# D_GND.net
KiCad netlist of a schematic drawn in Altium Designer
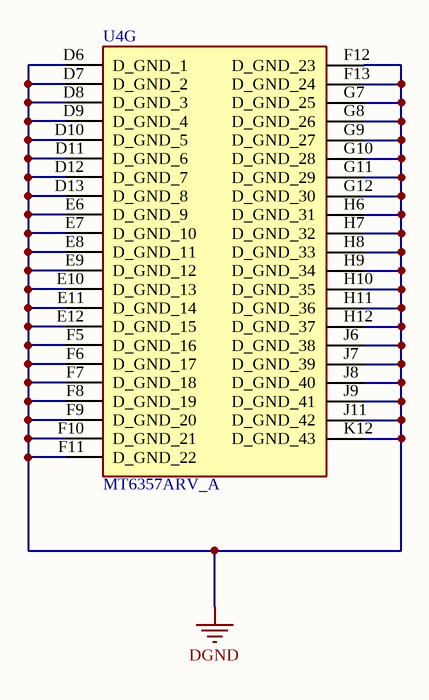
[diagram p0: D_GND.SchDoc]

(export (version "E")
  (design (tool "Eeschema 10.0.6"))
  (components
    (comp (ref "U4")
      (value "MT6357ARV_A")
      (footprint "BGA209C40P17X16_700X660X100")
      (description "Integrated Circuit")
      (fields
        (field (name "MANUFACTURER_PART_NUMBER") "MT6357ARV/A")
        (field (name "MOUSER PART NUMBER") "840-MT6357ARV/A")
      )
      (libsource (lib "kit") (part "MT6357ARV_A"))
    )
  )
  (nets
    (net (code "1") (name "DGND") (class "Default")
      (node (ref "U4") (pin "D10") (pinfunction "D_GND_5_D10") (pintype "passive"))
      (node (ref "U4") (pin "D11") (pinfunction "D_GND_6_D11") (pintype "passive"))
      (node (ref "U4") (pin "D12") (pinfunction "D_GND_7_D12") (pintype "passive"))
      (node (ref "U4") (pin "D13") (pinfunction "D_GND_8_D13") (pintype "passive"))
      (node (ref "U4") (pin "D6") (pinfunction "D_GND_1_D6") (pintype "passive"))
      (node (ref "U4") (pin "D7") (pinfunction "D_GND_2_D7") (pintype "passive"))
      (node (ref "U4") (pin "D8") (pinfunction "D_GND_3_D8") (pintype "passive"))
      (node (ref "U4") (pin "D9") (pinfunction "D_GND_4_D9") (pintype "passive"))
      (node (ref "U4") (pin "E10") (pinfunction "D_GND_13_E10") (pintype "passive"))
      (node (ref "U4") (pin "E11") (pinfunction "D_GND_14_E11") (pintype "passive"))
      (node (ref "U4") (pin "E12") (pinfunction "D_GND_15_E12") (pintype "passive"))
      (node (ref "U4") (pin "E6") (pinfunction "D_GND_9_E6") (pintype "passive"))
      (node (ref "U4") (pin "E7") (pinfunction "D_GND_10_E7") (pintype "passive"))
      (node (ref "U4") (pin "E8") (pinfunction "D_GND_11_E8") (pintype "passive"))
      (node (ref "U4") (pin "E9") (pinfunction "D_GND_12_E9") (pintype "passive"))
      (node (ref "U4") (pin "F10") (pinfunction "D_GND_21_F10") (pintype "passive"))
      (node (ref "U4") (pin "F11") (pinfunction "D_GND_22_F11") (pintype "passive"))
      (node (ref "U4") (pin "F12") (pinfunction "D_GND_23_F12") (pintype "passive"))
      (node (ref "U4") (pin "F13") (pinfunction "D_GND_24_F13") (pintype "passive"))
      (node (ref "U4") (pin "F5") (pinfunction "D_GND_16_F5") (pintype "passive"))
      (node (ref "U4") (pin "F6") (pinfunction "D_GND_17_F6") (pintype "passive"))
      (node (ref "U4") (pin "F7") (pinfunction "D_GND_18_F7") (pintype "passive"))
      (node (ref "U4") (pin "F8") (pinfunction "D_GND_19_F8") (pintype "passive"))
      (node (ref "U4") (pin "F9") (pinfunction "D_GND_20_F9") (pintype "passive"))
      (node (ref "U4") (pin "G10") (pinfunction "D_GND_28_G10") (pintype "passive"))
      (node (ref "U4") (pin "G11") (pinfunction "D_GND_29_G11") (pintype "passive"))
      (node (ref "U4") (pin "G12") (pinfunction "D_GND_30_G12") (pintype "passive"))
      (node (ref "U4") (pin "G7") (pinfunction "D_GND_25_G7") (pintype "passive"))
      (node (ref "U4") (pin "G8") (pinfunction "D_GND_26_G8") (pintype "passive"))
      (node (ref "U4") (pin "G9") (pinfunction "D_GND_27_G9") (pintype "passive"))
      (node (ref "U4") (pin "H10") (pinfunction "D_GND_35_H10") (pintype "passive"))
      (node (ref "U4") (pin "H11") (pinfunction "D_GND_36_H11") (pintype "passive"))
      (node (ref "U4") (pin "H12") (pinfunction "D_GND_37_H12") (pintype "passive"))
      (node (ref "U4") (pin "H6") (pinfunction "D_GND_31_H6") (pintype "passive"))
      (node (ref "U4") (pin "H7") (pinfunction "D_GND_32_H7") (pintype "passive"))
      (node (ref "U4") (pin "H8") (pinfunction "D_GND_33_H8") (pintype "passive"))
      (node (ref "U4") (pin "H9") (pinfunction "D_GND_34_H9") (pintype "passive"))
      (node (ref "U4") (pin "J11") (pinfunction "D_GND_42_J11") (pintype "passive"))
      (node (ref "U4") (pin "J6") (pinfunction "D_GND_38_J6") (pintype "passive"))
      (node (ref "U4") (pin "J7") (pinfunction "D_GND_39_J7") (pintype "passive"))
      (node (ref "U4") (pin "J8") (pinfunction "D_GND_40_J8") (pintype "passive"))
      (node (ref "U4") (pin "J9") (pinfunction "D_GND_41_J9") (pintype "passive"))
      (node (ref "U4") (pin "K12") (pinfunction "D_GND_43_K12") (pintype "passive"))
    )
  )
)
